# sensor_interface_board_1_0_0.net
KiCad netlist of a schematic drawn in EAGLE
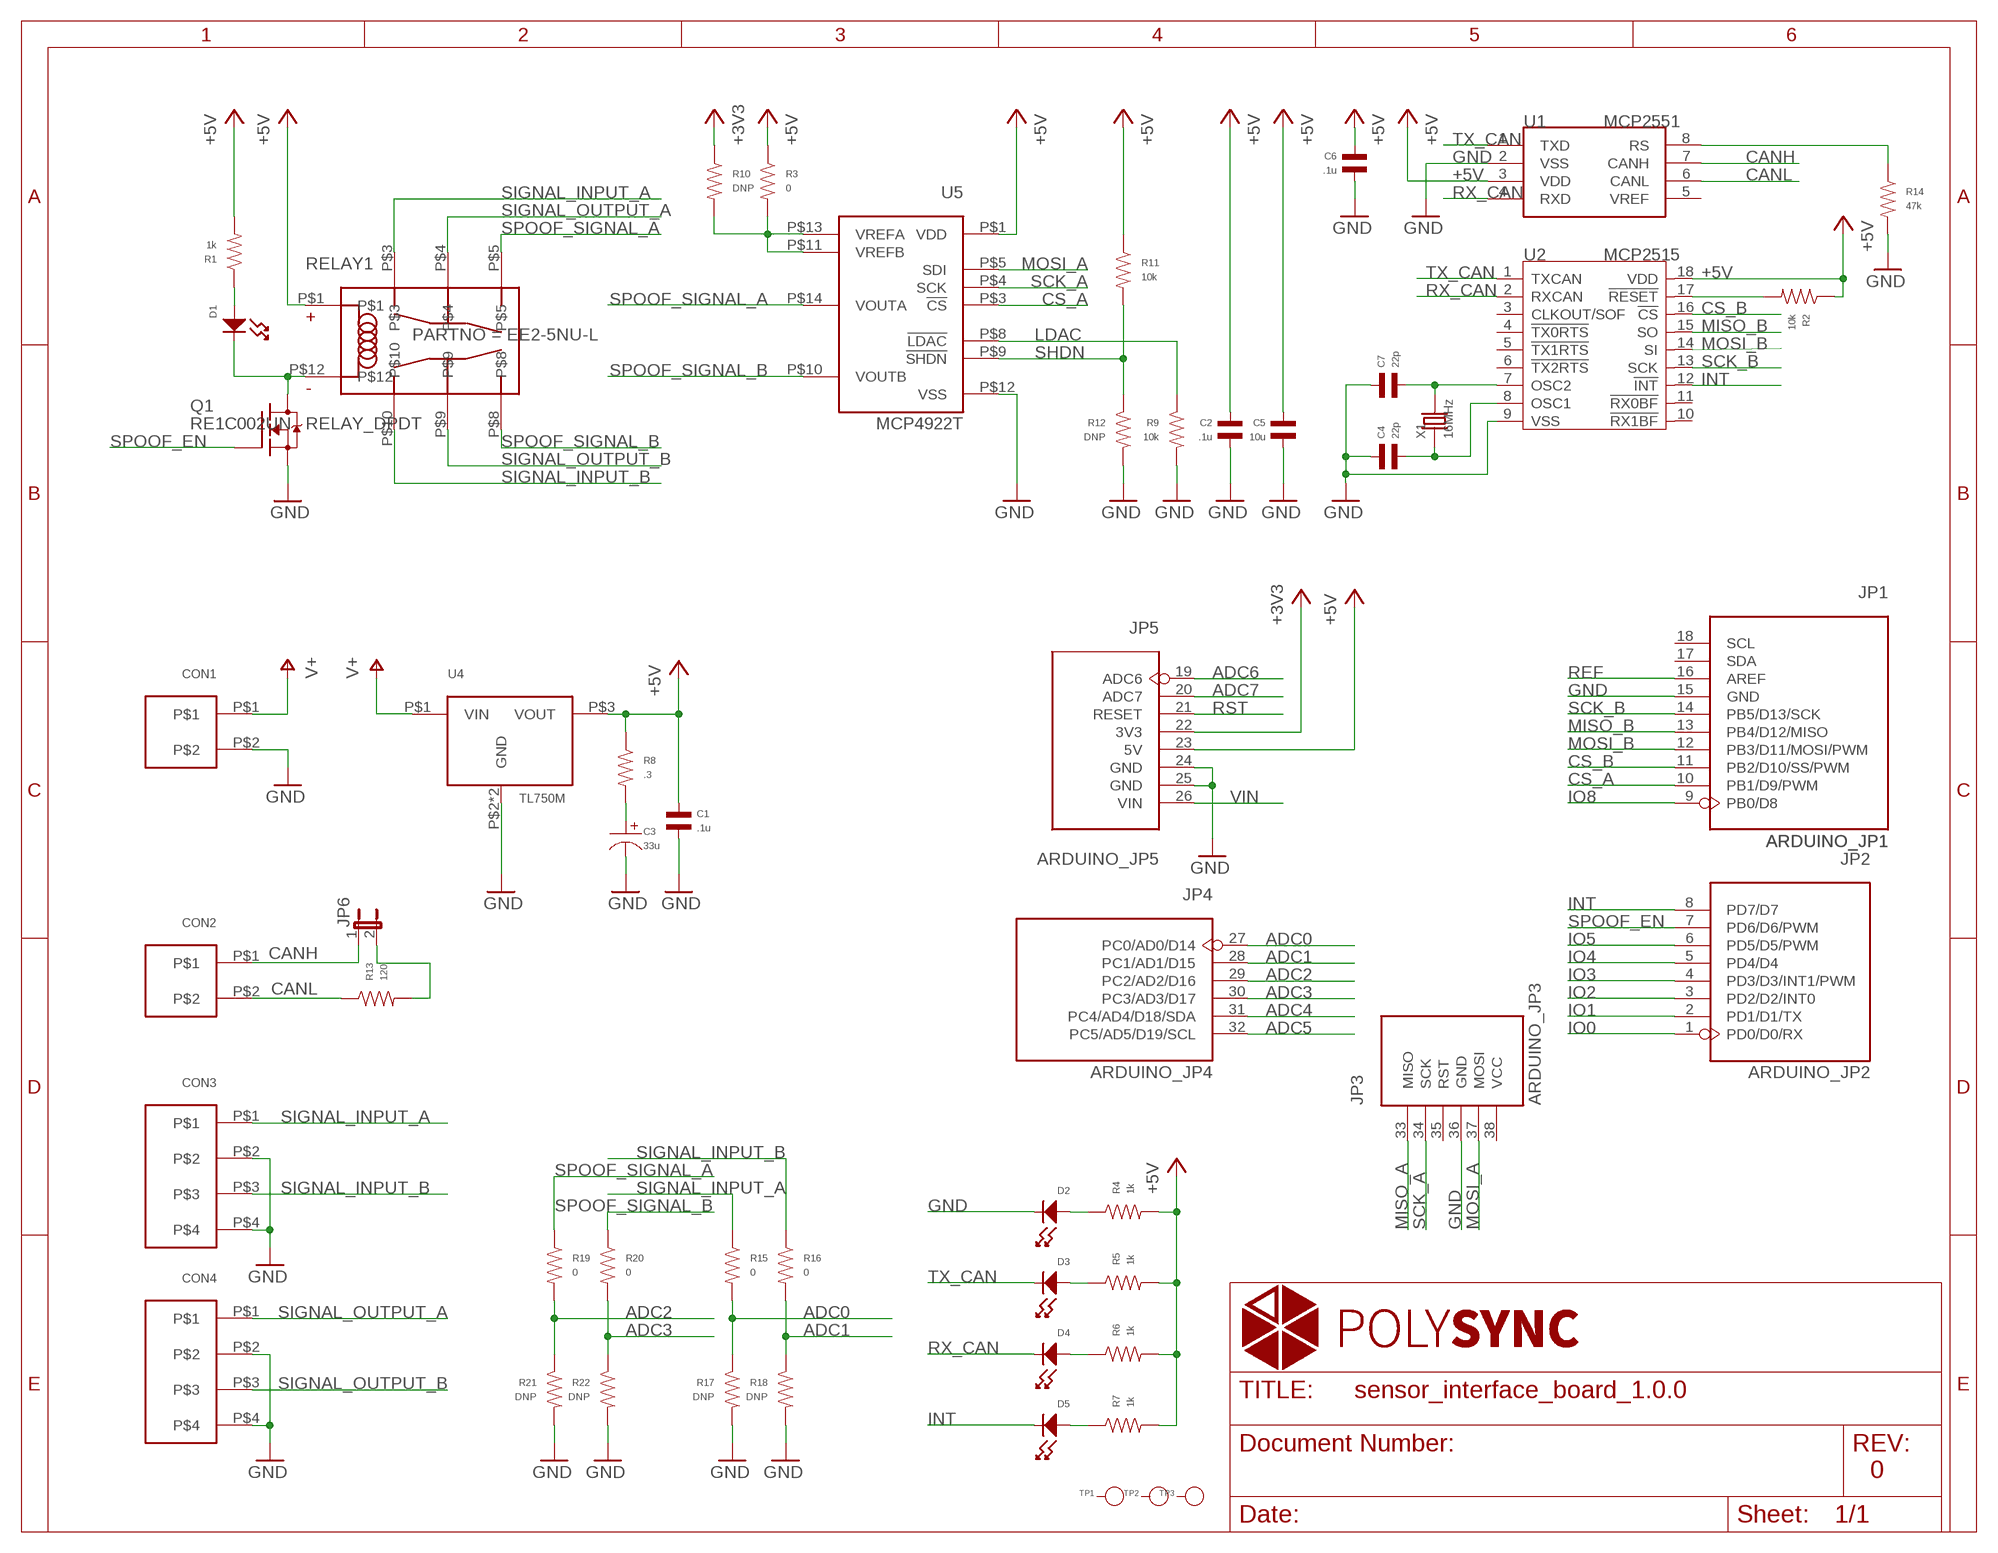
[diagram p0: schematic, sheet 1]

(export (version "E")
  (design (tool "Eeschema 10.0.6"))
  (components
    (comp (ref "C1")
      (value ".1u")
      (footprint "eagle-import:C0402")
      (libsource (lib "eagle-import") (part "CAPACITOR_NP_0402"))
    )
    (comp (ref "C2")
      (value ".1u")
      (footprint "eagle-import:C0402")
      (libsource (lib "eagle-import") (part "CAPACITOR_NP_0402"))
    )
    (comp (ref "C3")
      (value "33u")
      (footprint "eagle-import:CP1206")
      (libsource (lib "eagle-import") (part "CAPACITOR_P"))
    )
    (comp (ref "C4")
      (value "22p")
      (footprint "eagle-import:C0402")
      (libsource (lib "eagle-import") (part "CAPACITOR_NP_0402"))
    )
    (comp (ref "C5")
      (value "10u")
      (footprint "eagle-import:C0805")
      (libsource (lib "eagle-import") (part "CAPACITOR_NP_0805"))
    )
    (comp (ref "C6")
      (value ".1u")
      (footprint "eagle-import:C0402")
      (libsource (lib "eagle-import") (part "CAPACITOR_NP_0402"))
    )
    (comp (ref "C7")
      (value "22p")
      (footprint "eagle-import:C0402")
      (libsource (lib "eagle-import") (part "CAPACITOR_NP_0402"))
    )
    (comp (ref "CON1")
      (value "CON23.5MM")
      (footprint "eagle-import:PHOENIX_2_45")
      (libsource (lib "eagle-import") (part "CON23.5MM"))
    )
    (comp (ref "CON2")
      (value "CON23.5MM")
      (footprint "eagle-import:PHOENIX_2_45")
      (libsource (lib "eagle-import") (part "CON23.5MM"))
    )
    (comp (ref "CON3")
      (value "CON4")
      (footprint "eagle-import:PHOENIX_4_45")
      (libsource (lib "eagle-import") (part "CON4"))
    )
    (comp (ref "CON4")
      (value "CON4")
      (footprint "eagle-import:PHOENIX_4_45")
      (libsource (lib "eagle-import") (part "CON4"))
    )
    (comp (ref "D1")
      (value "LED_SINGLE-0603")
      (footprint "eagle-import:LED0603")
      (fields (field (name "HOUSEPART") "NO"))
      (libsource (lib "eagle-import") (part "LED_SINGLE-0603"))
    )
    (comp (ref "D2")
      (value "LED_SINGLE-0603")
      (footprint "eagle-import:LED0603")
      (fields (field (name "HOUSEPART") "NO"))
      (libsource (lib "eagle-import") (part "LED_SINGLE-0603"))
    )
    (comp (ref "D3")
      (value "LED_SINGLE-0603")
      (footprint "eagle-import:LED0603")
      (fields (field (name "HOUSEPART") "NO"))
      (libsource (lib "eagle-import") (part "LED_SINGLE-0603"))
    )
    (comp (ref "D4")
      (value "LED_SINGLE-0603")
      (footprint "eagle-import:LED0603")
      (fields (field (name "HOUSEPART") "NO"))
      (libsource (lib "eagle-import") (part "LED_SINGLE-0603"))
    )
    (comp (ref "D5")
      (value "LED_SINGLE-0603")
      (footprint "eagle-import:LED0603")
      (fields (field (name "HOUSEPART") "NO"))
      (libsource (lib "eagle-import") (part "LED_SINGLE-0603"))
    )
    (comp (ref "JP1")
      (value "ARDUINO_JP1")
      (footprint "eagle-import:ARDUINO_JP1")
      (libsource (lib "eagle-import") (part "ARDUINO_JP1"))
    )
    (comp (ref "JP2")
      (value "ARDUINO_JP2")
      (footprint "eagle-import:ARDUINO_JP2")
      (libsource (lib "eagle-import") (part "ARDUINO_JP2"))
    )
    (comp (ref "JP3")
      (value "ARDUINO_JP3")
      (footprint "eagle-import:ARDUINO_JP3")
      (libsource (lib "eagle-import") (part "ARDUINO_JP3"))
    )
    (comp (ref "JP4")
      (value "ARDUINO_JP4")
      (footprint "eagle-import:ARDUINO_JP4")
      (libsource (lib "eagle-import") (part "ARDUINO_JP4"))
    )
    (comp (ref "JP5")
      (value "ARDUINO_JP5")
      (footprint "eagle-import:ARDUINO_JP5")
      (libsource (lib "eagle-import") (part "ARDUINO_JP5"))
    )
    (comp (ref "JP6")
      (value "JP1E")
      (footprint "eagle-import:JP1")
      (libsource (lib "eagle-import") (part "JP1E"))
    )
    (comp (ref "Q1")
      (value "RE1C002UN")
      (footprint "eagle-import:EMT3F")
      (libsource (lib "eagle-import") (part "RE1C002UN"))
    )
    (comp (ref "R1")
      (value "1k")
      (footprint "eagle-import:R0402")
      (libsource (lib "eagle-import") (part "RESISTOR_0402"))
    )
    (comp (ref "R2")
      (value "10k")
      (footprint "eagle-import:R0402")
      (libsource (lib "eagle-import") (part "RESISTOR_0402"))
    )
    (comp (ref "R3")
      (value "0")
      (footprint "eagle-import:R0402")
      (libsource (lib "eagle-import") (part "RESISTOR_0402"))
    )
    (comp (ref "R4")
      (value "1k")
      (footprint "eagle-import:R0402")
      (libsource (lib "eagle-import") (part "RESISTOR_0402"))
    )
    (comp (ref "R5")
      (value "1k")
      (footprint "eagle-import:R0402")
      (libsource (lib "eagle-import") (part "RESISTOR_0402"))
    )
    (comp (ref "R6")
      (value "1k")
      (footprint "eagle-import:R0402")
      (libsource (lib "eagle-import") (part "RESISTOR_0402"))
    )
    (comp (ref "R7")
      (value "1k")
      (footprint "eagle-import:R0402")
      (libsource (lib "eagle-import") (part "RESISTOR_0402"))
    )
    (comp (ref "R8")
      (value ".3")
      (footprint "eagle-import:R0402")
      (libsource (lib "eagle-import") (part "RESISTOR_0402"))
    )
    (comp (ref "R9")
      (value "10k")
      (footprint "eagle-import:R0402")
      (libsource (lib "eagle-import") (part "RESISTOR_0402"))
    )
    (comp (ref "R10")
      (value "DNP")
      (footprint "eagle-import:R0402")
      (libsource (lib "eagle-import") (part "RESISTOR_0402"))
    )
    (comp (ref "R11")
      (value "10k")
      (footprint "eagle-import:R0402")
      (libsource (lib "eagle-import") (part "RESISTOR_0402"))
    )
    (comp (ref "R12")
      (value "DNP")
      (footprint "eagle-import:R0402")
      (libsource (lib "eagle-import") (part "RESISTOR_0402"))
    )
    (comp (ref "R13")
      (value "120")
      (footprint "eagle-import:R0402")
      (libsource (lib "eagle-import") (part "RESISTOR_0402"))
    )
    (comp (ref "R14")
      (value "47k")
      (footprint "eagle-import:R0402")
      (libsource (lib "eagle-import") (part "RESISTOR_0402"))
    )
    (comp (ref "R15")
      (value "0")
      (footprint "eagle-import:R0402")
      (libsource (lib "eagle-import") (part "RESISTOR_0402"))
    )
    (comp (ref "R16")
      (value "0")
      (footprint "eagle-import:R0402")
      (libsource (lib "eagle-import") (part "RESISTOR_0402"))
    )
    (comp (ref "R17")
      (value "DNP")
      (footprint "eagle-import:R0402")
      (libsource (lib "eagle-import") (part "RESISTOR_0402"))
    )
    (comp (ref "R18")
      (value "DNP")
      (footprint "eagle-import:R0402")
      (libsource (lib "eagle-import") (part "RESISTOR_0402"))
    )
    (comp (ref "R19")
      (value "0")
      (footprint "eagle-import:R0402")
      (libsource (lib "eagle-import") (part "RESISTOR_0402"))
    )
    (comp (ref "R20")
      (value "0")
      (footprint "eagle-import:R0402")
      (libsource (lib "eagle-import") (part "RESISTOR_0402"))
    )
    (comp (ref "R21")
      (value "DNP")
      (footprint "eagle-import:R0402")
      (libsource (lib "eagle-import") (part "RESISTOR_0402"))
    )
    (comp (ref "R22")
      (value "DNP")
      (footprint "eagle-import:R0402")
      (libsource (lib "eagle-import") (part "RESISTOR_0402"))
    )
    (comp (ref "RELAY1")
      (value "RELAY_DPDT")
      (footprint "eagle-import:KEMET_EE2")
      (fields (field (name "PARTNO") "EE2-5NU-L"))
      (libsource (lib "eagle-import") (part "RELAY_DPDT"))
    )
    (comp (ref "TP1")
      (value "PAD-TEST-POINT'4545'")
      (footprint "eagle-import:TP_4545")
      (fields (field (name "PARTNO") "DNP"))
      (libsource (lib "eagle-import") (part "PAD-TEST-POINT'4545'"))
    )
    (comp (ref "TP2")
      (value "PAD-TEST-POINT'4545'")
      (footprint "eagle-import:TP_4545")
      (fields (field (name "PARTNO") "DNP"))
      (libsource (lib "eagle-import") (part "PAD-TEST-POINT'4545'"))
    )
    (comp (ref "TP3")
      (value "PAD-TEST-POINT'4545'")
      (footprint "eagle-import:TP_4545")
      (fields (field (name "PARTNO") "DNP"))
      (libsource (lib "eagle-import") (part "PAD-TEST-POINT'4545'"))
    )
    (comp (ref "U1")
      (value "MCP2551")
      (footprint "eagle-import:SOIC8-6.0")
      (libsource (lib "eagle-import") (part "MCP2551-SOIC8"))
    )
    (comp (ref "U2")
      (value "MCP2515")
      (footprint "eagle-import:SOIC18")
      (libsource (lib "eagle-import") (part "MCP2515-SOIC18"))
    )
    (comp (ref "U4")
      (value "TL750M")
      (footprint "eagle-import:TO-263")
      (libsource (lib "eagle-import") (part "TL750M"))
    )
    (comp (ref "U5")
      (value "MCP4922T")
      (footprint "eagle-import:TSSOP-14")
      (libsource (lib "eagle-import") (part "MCP4922T"))
    )
    (comp (ref "X1")
      (value "16MHz")
      (footprint "eagle-import:HC49UP")
      (libsource (lib "eagle-import") (part "CRYSTAL-HC49UP"))
    )
  )
  (nets
    (net (code "1") (name "+3V3") (class "Default")
      (node (ref "JP5") (pin "22") (pinfunction "3V3_22") (pintype "bidirectional"))
      (node (ref "R10") (pin "P$1") (pinfunction "P$1_P$1") (pintype "passive"))
    )
    (net (code "2") (name "+5V") (class "Default")
      (node (ref "C1") (pin "P$1") (pinfunction "P$1_P$1") (pintype "passive"))
      (node (ref "C2") (pin "P$1") (pinfunction "P$1_P$1") (pintype "passive"))
      (node (ref "C5") (pin "P$1") (pinfunction "P$1_P$1") (pintype "passive"))
      (node (ref "C6") (pin "P$1") (pinfunction "P$1_P$1") (pintype "passive"))
      (node (ref "JP5") (pin "23") (pinfunction "5V_23") (pintype "bidirectional"))
      (node (ref "R1") (pin "P$2") (pinfunction "P$2_P$2") (pintype "passive"))
      (node (ref "R11") (pin "P$1") (pinfunction "P$1_P$1") (pintype "passive"))
      (node (ref "R2") (pin "P$1") (pinfunction "P$1_P$1") (pintype "passive"))
      (node (ref "R3") (pin "P$1") (pinfunction "P$1_P$1") (pintype "passive"))
      (node (ref "R4") (pin "P$2") (pinfunction "P$2_P$2") (pintype "passive"))
      (node (ref "R5") (pin "P$2") (pinfunction "P$2_P$2") (pintype "passive"))
      (node (ref "R6") (pin "P$2") (pinfunction "P$2_P$2") (pintype "passive"))
      (node (ref "R7") (pin "P$2") (pinfunction "P$2_P$2") (pintype "passive"))
      (node (ref "R8") (pin "P$1") (pinfunction "P$1_P$1") (pintype "passive"))
      (node (ref "RELAY1") (pin "P$1") (pinfunction "P$1_P$1") (pintype "bidirectional"))
      (node (ref "U1") (pin "3") (pinfunction "VDD_3") (pintype "bidirectional"))
      (node (ref "U2") (pin "18") (pinfunction "VDD_18") (pintype "power_in"))
      (node (ref "U4") (pin "P$3") (pinfunction "VOUT_P$3") (pintype "bidirectional"))
      (node (ref "U5") (pin "P$1") (pinfunction "VDD_P$1") (pintype "bidirectional"))
    )
    (net (code "3") (name "/ADC0") (class "Default")
      (node (ref "JP4") (pin "27") (pinfunction "PC0/AD0/D14_27") (pintype "bidirectional"))
      (node (ref "R15") (pin "P$2") (pinfunction "P$2_P$2") (pintype "passive"))
      (node (ref "R17") (pin "P$1") (pinfunction "P$1_P$1") (pintype "passive"))
    )
    (net (code "4") (name "/ADC1") (class "Default")
      (node (ref "JP4") (pin "28") (pinfunction "PC1/AD1/D15_28") (pintype "bidirectional"))
      (node (ref "R16") (pin "P$2") (pinfunction "P$2_P$2") (pintype "passive"))
      (node (ref "R18") (pin "P$1") (pinfunction "P$1_P$1") (pintype "passive"))
    )
    (net (code "5") (name "/ADC2") (class "Default")
      (node (ref "JP4") (pin "29") (pinfunction "PC2/AD2/D16_29") (pintype "bidirectional"))
      (node (ref "R19") (pin "P$2") (pinfunction "P$2_P$2") (pintype "passive"))
      (node (ref "R21") (pin "P$1") (pinfunction "P$1_P$1") (pintype "passive"))
    )
    (net (code "6") (name "/ADC3") (class "Default")
      (node (ref "JP4") (pin "30") (pinfunction "PC3/AD3/D17_30") (pintype "bidirectional"))
      (node (ref "R20") (pin "P$2") (pinfunction "P$2_P$2") (pintype "passive"))
      (node (ref "R22") (pin "P$1") (pinfunction "P$1_P$1") (pintype "passive"))
    )
    (net (code "7") (name "/ADC4") (class "Default")
      (node (ref "JP4") (pin "31") (pinfunction "PC4/AD4/D18/SDA_31") (pintype "bidirectional"))
    )
    (net (code "8") (name "/ADC5") (class "Default")
      (node (ref "JP4") (pin "32") (pinfunction "PC5/AD5/D19/SCL_32") (pintype "bidirectional"))
    )
    (net (code "9") (name "/ADC6") (class "Default")
      (node (ref "JP5") (pin "19") (pinfunction "ADC6_19") (pintype "bidirectional"))
    )
    (net (code "10") (name "/ADC7") (class "Default")
      (node (ref "JP5") (pin "20") (pinfunction "ADC7_20") (pintype "bidirectional"))
    )
    (net (code "11") (name "/CANH") (class "Default")
      (node (ref "CON2") (pin "P$1") (pinfunction "P$1_P$1") (pintype "bidirectional"))
      (node (ref "JP6") (pin "1") (pinfunction "1_1") (pintype "passive"))
      (node (ref "U1") (pin "7") (pinfunction "CANH_7") (pintype "bidirectional"))
    )
    (net (code "12") (name "/CANL") (class "Default")
      (node (ref "CON2") (pin "P$2") (pinfunction "P$2_P$2") (pintype "bidirectional"))
      (node (ref "R13") (pin "P$1") (pinfunction "P$1_P$1") (pintype "passive"))
      (node (ref "U1") (pin "6") (pinfunction "CANL_6") (pintype "bidirectional"))
    )
    (net (code "13") (name "/CS_A") (class "Default")
      (node (ref "JP1") (pin "10") (pinfunction "PB1/D9/PWM_10") (pintype "bidirectional"))
      (node (ref "U5") (pin "P$3") (pinfunction "~{CS}_P$3") (pintype "bidirectional"))
    )
    (net (code "14") (name "/CS_B") (class "Default")
      (node (ref "JP1") (pin "11") (pinfunction "PB2/D10/SS/PWM_11") (pintype "bidirectional"))
      (node (ref "U2") (pin "16") (pinfunction "~{CS}_16") (pintype "input"))
    )
    (net (code "15") (name "/INT") (class "Default")
      (node (ref "D5") (pin "CATHODE") (pinfunction "CATHODE_CATHODE") (pintype "power_in"))
      (node (ref "JP2") (pin "8") (pinfunction "PD7/D7_8") (pintype "bidirectional"))
      (node (ref "U2") (pin "12") (pinfunction "~{INT}_12") (pintype "output"))
    )
    (net (code "16") (name "/IO0") (class "Default")
      (node (ref "JP2") (pin "1") (pinfunction "PD0/D0/RX_1") (pintype "bidirectional"))
    )
    (net (code "17") (name "/IO1") (class "Default")
      (node (ref "JP2") (pin "2") (pinfunction "PD1/D1/TX_2") (pintype "bidirectional"))
    )
    (net (code "18") (name "/IO2") (class "Default")
      (node (ref "JP2") (pin "3") (pinfunction "PD2/D2/INT0_3") (pintype "bidirectional"))
    )
    (net (code "19") (name "/IO3") (class "Default")
      (node (ref "JP2") (pin "4") (pinfunction "PD3/D3/INT1/PWM_4") (pintype "bidirectional"))
    )
    (net (code "20") (name "/IO4") (class "Default")
      (node (ref "JP2") (pin "5") (pinfunction "PD4/D4_5") (pintype "bidirectional"))
    )
    (net (code "21") (name "/IO5") (class "Default")
      (node (ref "JP2") (pin "6") (pinfunction "PD5/D5/PWM_6") (pintype "bidirectional"))
    )
    (net (code "22") (name "/IO8") (class "Default")
      (node (ref "JP1") (pin "9") (pinfunction "PB0/D8_9") (pintype "bidirectional"))
    )
    (net (code "23") (name "/LDAC") (class "Default")
      (node (ref "R9") (pin "P$1") (pinfunction "P$1_P$1") (pintype "passive"))
      (node (ref "U5") (pin "P$8") (pinfunction "~{LDAC}_P$8") (pintype "bidirectional"))
    )
    (net (code "24") (name "/MISO_A") (class "Default")
      (node (ref "JP3") (pin "33") (pinfunction "MISO_33") (pintype "bidirectional"))
    )
    (net (code "25") (name "/MISO_B") (class "Default")
      (node (ref "JP1") (pin "13") (pinfunction "PB4/D12/MISO_13") (pintype "bidirectional"))
      (node (ref "U2") (pin "15") (pinfunction "SO_15") (pintype "output"))
    )
    (net (code "26") (name "/MOSI_A") (class "Default")
      (node (ref "JP3") (pin "37") (pinfunction "MOSI_37") (pintype "bidirectional"))
      (node (ref "U5") (pin "P$5") (pinfunction "SDI_P$5") (pintype "bidirectional"))
    )
    (net (code "27") (name "/MOSI_B") (class "Default")
      (node (ref "JP1") (pin "12") (pinfunction "PB3/D11/MOSI/PWM_12") (pintype "bidirectional"))
      (node (ref "U2") (pin "14") (pinfunction "SI_14") (pintype "input"))
    )
    (net (code "28") (name "/REF") (class "Default")
      (node (ref "JP1") (pin "16") (pinfunction "AREF_16") (pintype "bidirectional"))
    )
    (net (code "29") (name "/RST") (class "Default")
      (node (ref "JP5") (pin "21") (pinfunction "RESET_21") (pintype "bidirectional"))
    )
    (net (code "30") (name "/RX_CAN") (class "Default")
      (node (ref "D4") (pin "CATHODE") (pinfunction "CATHODE_CATHODE") (pintype "power_in"))
      (node (ref "U1") (pin "4") (pinfunction "RXD_4") (pintype "bidirectional"))
      (node (ref "U2") (pin "2") (pinfunction "RXCAN_2") (pintype "input"))
    )
    (net (code "31") (name "/SCK_A") (class "Default")
      (node (ref "JP3") (pin "34") (pinfunction "SCK_34") (pintype "bidirectional"))
      (node (ref "U5") (pin "P$4") (pinfunction "SCK_P$4") (pintype "bidirectional"))
    )
    (net (code "32") (name "/SCK_B") (class "Default")
      (node (ref "JP1") (pin "14") (pinfunction "PB5/D13/SCK_14") (pintype "bidirectional"))
      (node (ref "U2") (pin "13") (pinfunction "SCK_13") (pintype "input"))
    )
    (net (code "33") (name "/SHDN") (class "Default")
      (node (ref "R11") (pin "P$2") (pinfunction "P$2_P$2") (pintype "passive"))
      (node (ref "R12") (pin "P$1") (pinfunction "P$1_P$1") (pintype "passive"))
      (node (ref "U5") (pin "P$9") (pinfunction "~{SHDN}_P$9") (pintype "bidirectional"))
    )
    (net (code "34") (name "/SIGNAL_INPUT_A") (class "Default")
      (node (ref "CON3") (pin "P$1") (pinfunction "P$1_P$1") (pintype "bidirectional"))
      (node (ref "R15") (pin "P$1") (pinfunction "P$1_P$1") (pintype "passive"))
      (node (ref "RELAY1") (pin "P$3") (pinfunction "P$3_P$3") (pintype "bidirectional"))
    )
    (net (code "35") (name "/SIGNAL_INPUT_B") (class "Default")
      (node (ref "CON3") (pin "P$3") (pinfunction "P$3_P$3") (pintype "bidirectional"))
      (node (ref "R16") (pin "P$1") (pinfunction "P$1_P$1") (pintype "passive"))
      (node (ref "RELAY1") (pin "P$10") (pinfunction "P$10_P$10") (pintype "bidirectional"))
    )
    (net (code "36") (name "/SIGNAL_OUTPUT_A") (class "Default")
      (node (ref "CON4") (pin "P$1") (pinfunction "P$1_P$1") (pintype "bidirectional"))
      (node (ref "RELAY1") (pin "P$4") (pinfunction "P$4_P$4") (pintype "bidirectional"))
    )
    (net (code "37") (name "/SIGNAL_OUTPUT_B") (class "Default")
      (node (ref "CON4") (pin "P$3") (pinfunction "P$3_P$3") (pintype "bidirectional"))
      (node (ref "RELAY1") (pin "P$9") (pinfunction "P$9_P$9") (pintype "bidirectional"))
    )
    (net (code "38") (name "/SPOOF_EN") (class "Default")
      (node (ref "JP2") (pin "7") (pinfunction "PD6/D6/PWM_7") (pintype "bidirectional"))
      (node (ref "Q1") (pin "P$1") (pinfunction "G_P$1") (pintype "passive"))
    )
    (net (code "39") (name "/SPOOF_SIGNAL_A") (class "Default")
      (node (ref "R19") (pin "P$1") (pinfunction "P$1_P$1") (pintype "passive"))
      (node (ref "RELAY1") (pin "P$5") (pinfunction "P$5_P$5") (pintype "bidirectional"))
      (node (ref "U5") (pin "P$14") (pinfunction "VOUTA_P$14") (pintype "bidirectional"))
    )
    (net (code "40") (name "/SPOOF_SIGNAL_B") (class "Default")
      (node (ref "R20") (pin "P$1") (pinfunction "P$1_P$1") (pintype "passive"))
      (node (ref "RELAY1") (pin "P$8") (pinfunction "P$8_P$8") (pintype "bidirectional"))
      (node (ref "U5") (pin "P$10") (pinfunction "VOUTB_P$10") (pintype "bidirectional"))
    )
    (net (code "41") (name "/TX_CAN") (class "Default")
      (node (ref "D3") (pin "CATHODE") (pinfunction "CATHODE_CATHODE") (pintype "power_in"))
      (node (ref "U1") (pin "1") (pinfunction "TXD_1") (pintype "bidirectional"))
      (node (ref "U2") (pin "1") (pinfunction "TXCAN_1") (pintype "output"))
    )
    (net (code "42") (name "/VIN") (class "Default")
      (node (ref "JP5") (pin "26") (pinfunction "VIN_26") (pintype "bidirectional"))
    )
    (net (code "43") (name "GND") (class "Default")
      (node (ref "C1") (pin "P$2") (pinfunction "P$2_P$2") (pintype "passive"))
      (node (ref "C2") (pin "P$2") (pinfunction "P$2_P$2") (pintype "passive"))
      (node (ref "C3") (pin "P$2") (pinfunction "P$2_P$2") (pintype "passive"))
      (node (ref "C4") (pin "P$1") (pinfunction "P$1_P$1") (pintype "passive"))
      (node (ref "C5") (pin "P$2") (pinfunction "P$2_P$2") (pintype "passive"))
      (node (ref "C6") (pin "P$2") (pinfunction "P$2_P$2") (pintype "passive"))
      (node (ref "C7") (pin "P$1") (pinfunction "P$1_P$1") (pintype "passive"))
      (node (ref "CON1") (pin "P$2") (pinfunction "P$2_P$2") (pintype "bidirectional"))
      (node (ref "CON3") (pin "P$2") (pinfunction "P$2_P$2") (pintype "bidirectional"))
      (node (ref "CON3") (pin "P$4") (pinfunction "P$4_P$4") (pintype "bidirectional"))
      (node (ref "CON4") (pin "P$2") (pinfunction "P$2_P$2") (pintype "bidirectional"))
      (node (ref "CON4") (pin "P$4") (pinfunction "P$4_P$4") (pintype "bidirectional"))
      (node (ref "D2") (pin "CATHODE") (pinfunction "CATHODE_CATHODE") (pintype "power_in"))
      (node (ref "JP1") (pin "15") (pinfunction "GND_15") (pintype "bidirectional"))
      (node (ref "JP3") (pin "36") (pinfunction "GND_36") (pintype "bidirectional"))
      (node (ref "JP5") (pin "24") (pinfunction "GND_24") (pintype "bidirectional"))
      (node (ref "JP5") (pin "25") (pinfunction "GND_25") (pintype "bidirectional"))
      (node (ref "Q1") (pin "P$2") (pinfunction "S_P$2") (pintype "passive"))
      (node (ref "R12") (pin "P$2") (pinfunction "P$2_P$2") (pintype "passive"))
      (node (ref "R14") (pin "P$2") (pinfunction "P$2_P$2") (pintype "passive"))
      (node (ref "R17") (pin "P$2") (pinfunction "P$2_P$2") (pintype "passive"))
      (node (ref "R18") (pin "P$2") (pinfunction "P$2_P$2") (pintype "passive"))
      (node (ref "R21") (pin "P$2") (pinfunction "P$2_P$2") (pintype "passive"))
      (node (ref "R22") (pin "P$2") (pinfunction "P$2_P$2") (pintype "passive"))
      (node (ref "R9") (pin "P$2") (pinfunction "P$2_P$2") (pintype "passive"))
      (node (ref "U1") (pin "2") (pinfunction "VSS_2") (pintype "bidirectional"))
      (node (ref "U2") (pin "9") (pinfunction "VSS_9") (pintype "power_in"))
      (node (ref "U4") (pin "P$2") (pinfunction "GND_P$2") (pintype "bidirectional"))
      (node (ref "U4") (pin "P$4") (pinfunction "GND_P$4") (pintype "bidirectional"))
      (node (ref "U5") (pin "P$12") (pinfunction "VSS_P$12") (pintype "bidirectional"))
    )
    (net (code "44") (name "Net-(C3-PadP$1)") (class "Default")
      (node (ref "C3") (pin "P$1") (pinfunction "P$1_P$1") (pintype "passive"))
      (node (ref "R8") (pin "P$2") (pinfunction "P$2_P$2") (pintype "passive"))
    )
    (net (code "45") (name "Net-(D1-PadANODE)") (class "Default")
      (node (ref "D1") (pin "ANODE") (pinfunction "ANODE_ANODE") (pintype "power_in"))
      (node (ref "R1") (pin "P$1") (pinfunction "P$1_P$1") (pintype "passive"))
    )
    (net (code "46") (name "Net-(D2-PadANODE)") (class "Default")
      (node (ref "D2") (pin "ANODE") (pinfunction "ANODE_ANODE") (pintype "power_in"))
      (node (ref "R4") (pin "P$1") (pinfunction "P$1_P$1") (pintype "passive"))
    )
    (net (code "47") (name "Net-(D3-PadANODE)") (class "Default")
      (node (ref "D3") (pin "ANODE") (pinfunction "ANODE_ANODE") (pintype "power_in"))
      (node (ref "R5") (pin "P$1") (pinfunction "P$1_P$1") (pintype "passive"))
    )
    (net (code "48") (name "Net-(D4-PadANODE)") (class "Default")
      (node (ref "D4") (pin "ANODE") (pinfunction "ANODE_ANODE") (pintype "power_in"))
      (node (ref "R6") (pin "P$1") (pinfunction "P$1_P$1") (pintype "passive"))
    )
    (net (code "49") (name "Net-(D5-PadANODE)") (class "Default")
      (node (ref "D5") (pin "ANODE") (pinfunction "ANODE_ANODE") (pintype "power_in"))
      (node (ref "R7") (pin "P$1") (pinfunction "P$1_P$1") (pintype "passive"))
    )
    (net (code "50") (name "Net-(JP6-Pad2)") (class "Default")
      (node (ref "JP6") (pin "2") (pinfunction "2_2") (pintype "passive"))
      (node (ref "R13") (pin "P$2") (pinfunction "P$2_P$2") (pintype "passive"))
    )
    (net (code "51") (name "Net-(Q1-D)") (class "Default")
      (node (ref "D1") (pin "CATHODE") (pinfunction "CATHODE_CATHODE") (pintype "power_in"))
      (node (ref "Q1") (pin "P$3") (pinfunction "D_P$3") (pintype "passive"))
      (node (ref "RELAY1") (pin "P$12") (pinfunction "P$12_P$12") (pintype "bidirectional"))
    )
    (net (code "52") (name "Net-(U1-RS)") (class "Default")
      (node (ref "R14") (pin "P$1") (pinfunction "P$1_P$1") (pintype "passive"))
      (node (ref "U1") (pin "8") (pinfunction "RS_8") (pintype "bidirectional"))
    )
    (net (code "53") (name "Net-(U2-OSC1)") (class "Default")
      (node (ref "C4") (pin "P$2") (pinfunction "P$2_P$2") (pintype "passive"))
      (node (ref "U2") (pin "8") (pinfunction "OSC1_8") (pintype "input"))
      (node (ref "X1") (pin "1") (pinfunction "1_1") (pintype "passive"))
    )
    (net (code "54") (name "Net-(U2-OSC2)") (class "Default")
      (node (ref "C7") (pin "P$2") (pinfunction "P$2_P$2") (pintype "passive"))
      (node (ref "U2") (pin "7") (pinfunction "OSC2_7") (pintype "output"))
      (node (ref "X1") (pin "2") (pinfunction "2_2") (pintype "passive"))
    )
    (net (code "55") (name "Net-(U2-~{RESET})") (class "Default")
      (node (ref "R2") (pin "P$2") (pinfunction "P$2_P$2") (pintype "passive"))
      (node (ref "U2") (pin "17") (pinfunction "~{RESET}_17") (pintype "input"))
    )
    (net (code "56") (name "Net-(U5-VREFA)") (class "Default")
      (node (ref "R10") (pin "P$2") (pinfunction "P$2_P$2") (pintype "passive"))
      (node (ref "R3") (pin "P$2") (pinfunction "P$2_P$2") (pintype "passive"))
      (node (ref "U5") (pin "P$11") (pinfunction "VREFB_P$11") (pintype "bidirectional"))
      (node (ref "U5") (pin "P$13") (pinfunction "VREFA_P$13") (pintype "bidirectional"))
    )
    (net (code "57") (name "V+") (class "Default")
      (node (ref "CON1") (pin "P$1") (pinfunction "P$1_P$1") (pintype "bidirectional"))
      (node (ref "U4") (pin "P$1") (pinfunction "VIN_P$1") (pintype "bidirectional"))
    )
    (net (code "58") (name "unconnected-(JP1-SCL-Pad18)") (class "Default")
      (node (ref "JP1") (pin "18") (pinfunction "SCL_18") (pintype "bidirectional"))
    )
    (net (code "59") (name "unconnected-(JP1-SDA-Pad17)") (class "Default")
      (node (ref "JP1") (pin "17") (pinfunction "SDA_17") (pintype "bidirectional"))
    )
    (net (code "60") (name "unconnected-(JP3-RST-Pad35)") (class "Default")
      (node (ref "JP3") (pin "35") (pinfunction "RST_35") (pintype "bidirectional"))
    )
    (net (code "61") (name "unconnected-(JP3-VCC-Pad38)") (class "Default")
      (node (ref "JP3") (pin "38") (pinfunction "VCC_38") (pintype "bidirectional"))
    )
    (net (code "62") (name "unconnected-(TP1-PadT)") (class "Default")
      (node (ref "TP1") (pin "T") (pinfunction "T_T") (pintype "bidirectional"))
    )
    (net (code "63") (name "unconnected-(TP2-PadT)") (class "Default")
      (node (ref "TP2") (pin "T") (pinfunction "T_T") (pintype "bidirectional"))
    )
    (net (code "64") (name "unconnected-(TP3-PadT)") (class "Default")
      (node (ref "TP3") (pin "T") (pinfunction "T_T") (pintype "bidirectional"))
    )
    (net (code "65") (name "unconnected-(U1-VREF-Pad5)") (class "Default")
      (node (ref "U1") (pin "5") (pinfunction "VREF_5") (pintype "bidirectional"))
    )
    (net (code "66") (name "unconnected-(U2-CLKOUT{slash}SOF-Pad3)") (class "Default")
      (node (ref "U2") (pin "3") (pinfunction "CLKOUT/SOF_3") (pintype "output"))
    )
    (net (code "67") (name "unconnected-(U2-~{RX0BF}-Pad11)") (class "Default")
      (node (ref "U2") (pin "11") (pinfunction "~{RX0BF}_11") (pintype "output"))
    )
    (net (code "68") (name "unconnected-(U2-~{RX1BF}-Pad10)") (class "Default")
      (node (ref "U2") (pin "10") (pinfunction "~{RX1BF}_10") (pintype "output"))
    )
    (net (code "69") (name "unconnected-(U2-~{TX0RTS}-Pad4)") (class "Default")
      (node (ref "U2") (pin "4") (pinfunction "~{TX0RTS}_4") (pintype "input"))
    )
    (net (code "70") (name "unconnected-(U2-~{TX1RTS}-Pad5)") (class "Default")
      (node (ref "U2") (pin "5") (pinfunction "~{TX1RTS}_5") (pintype "input"))
    )
    (net (code "71") (name "unconnected-(U2-~{TX2RTS}-Pad6)") (class "Default")
      (node (ref "U2") (pin "6") (pinfunction "~{TX2RTS}_6") (pintype "input"))
    )
  )
)
